# WhaleTagRecovery_3v2r1_EasyEDA.net
KiCad netlist of a schematic drawn in EasyEDA Pro
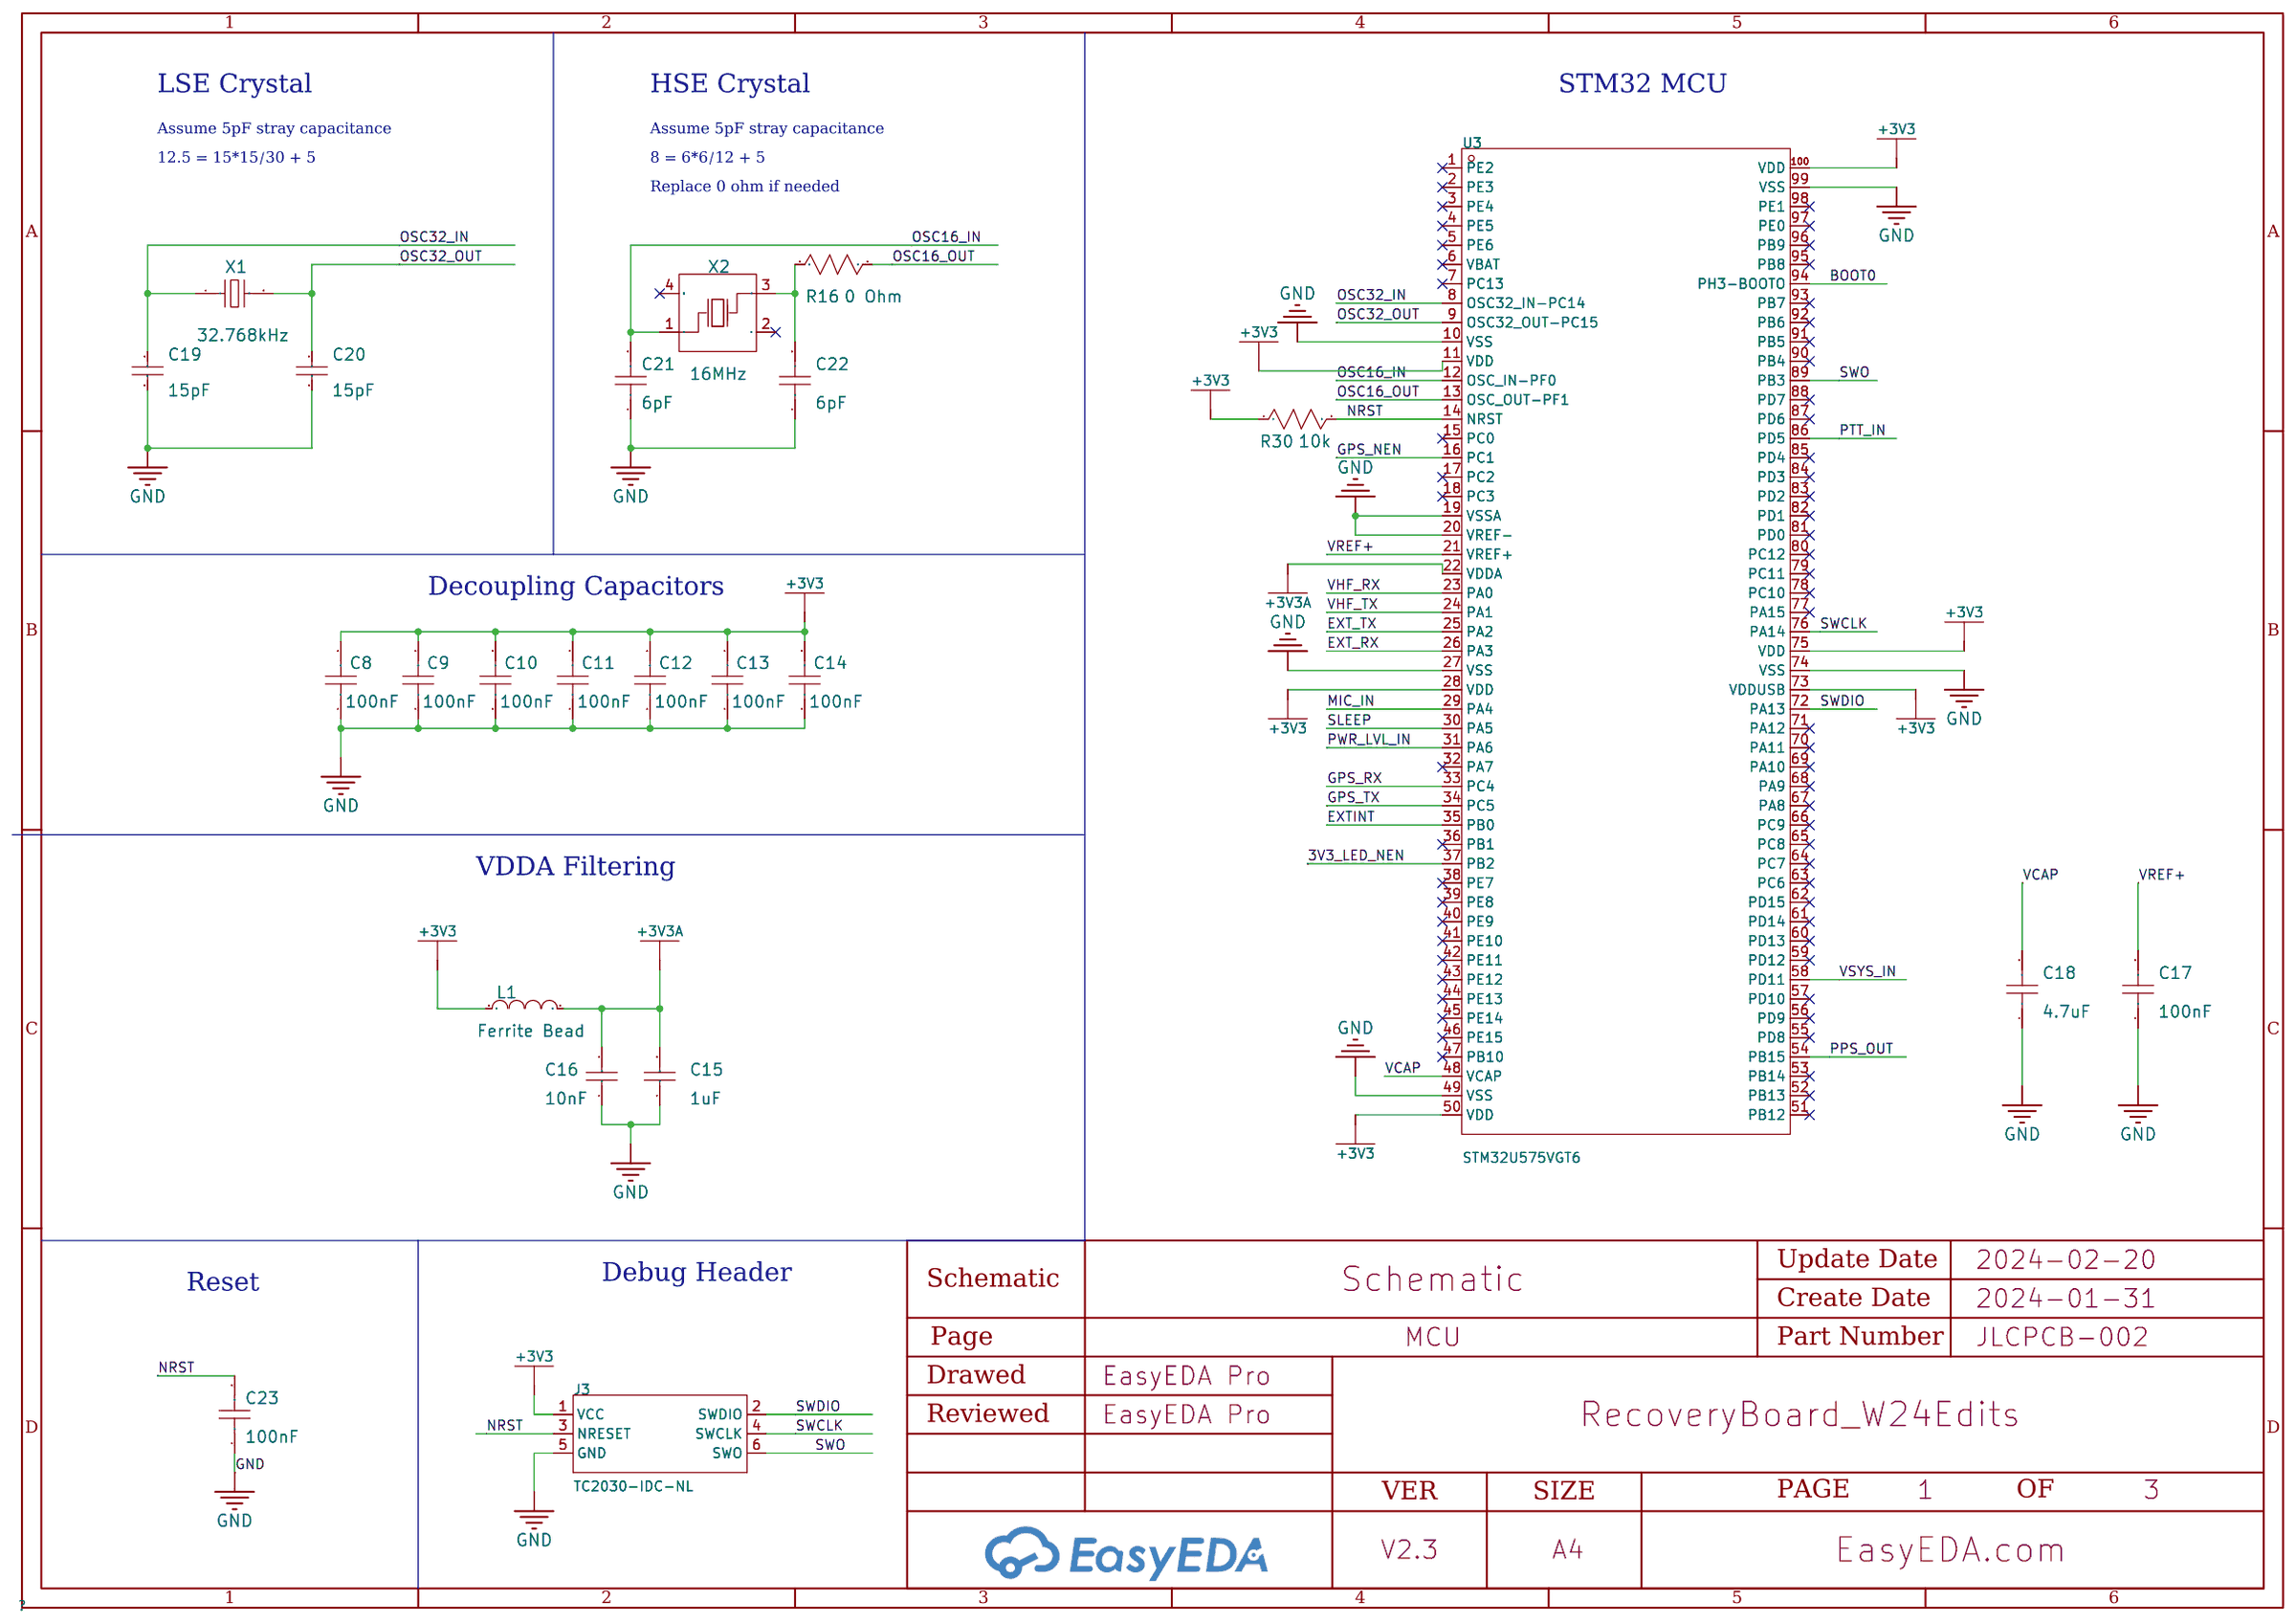
[diagram p0: MCU]
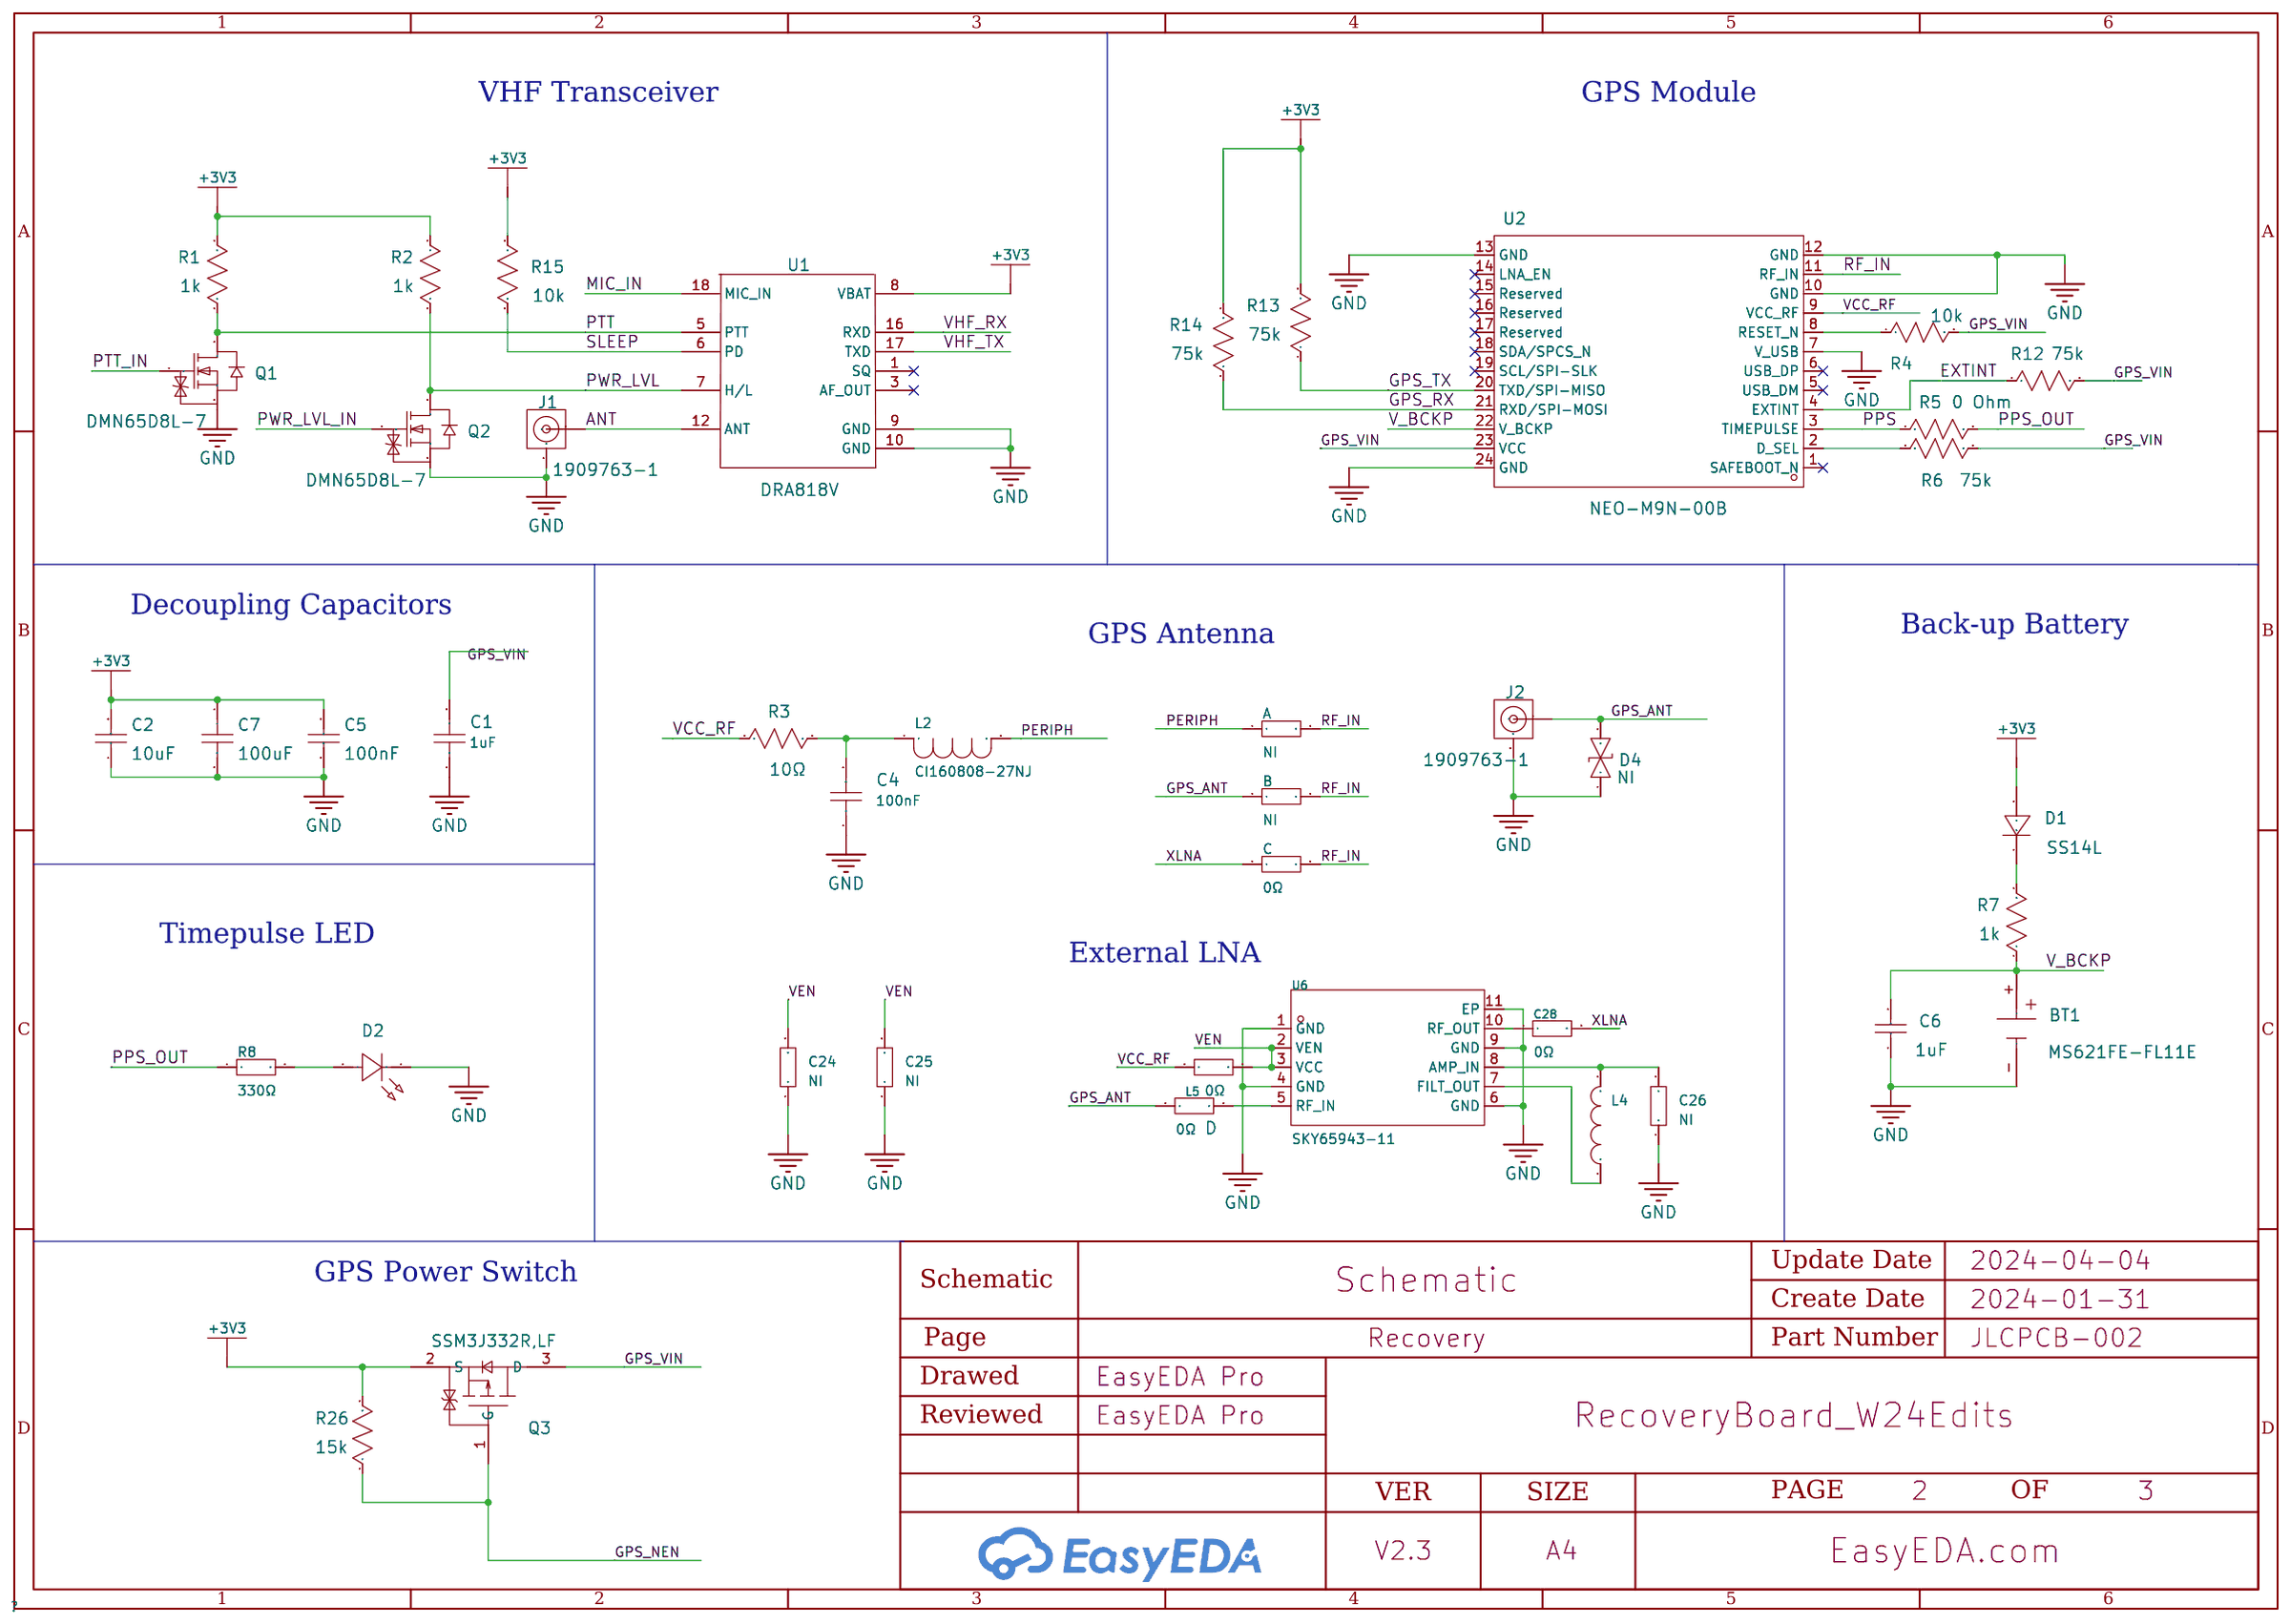
[diagram p1: Recovery]
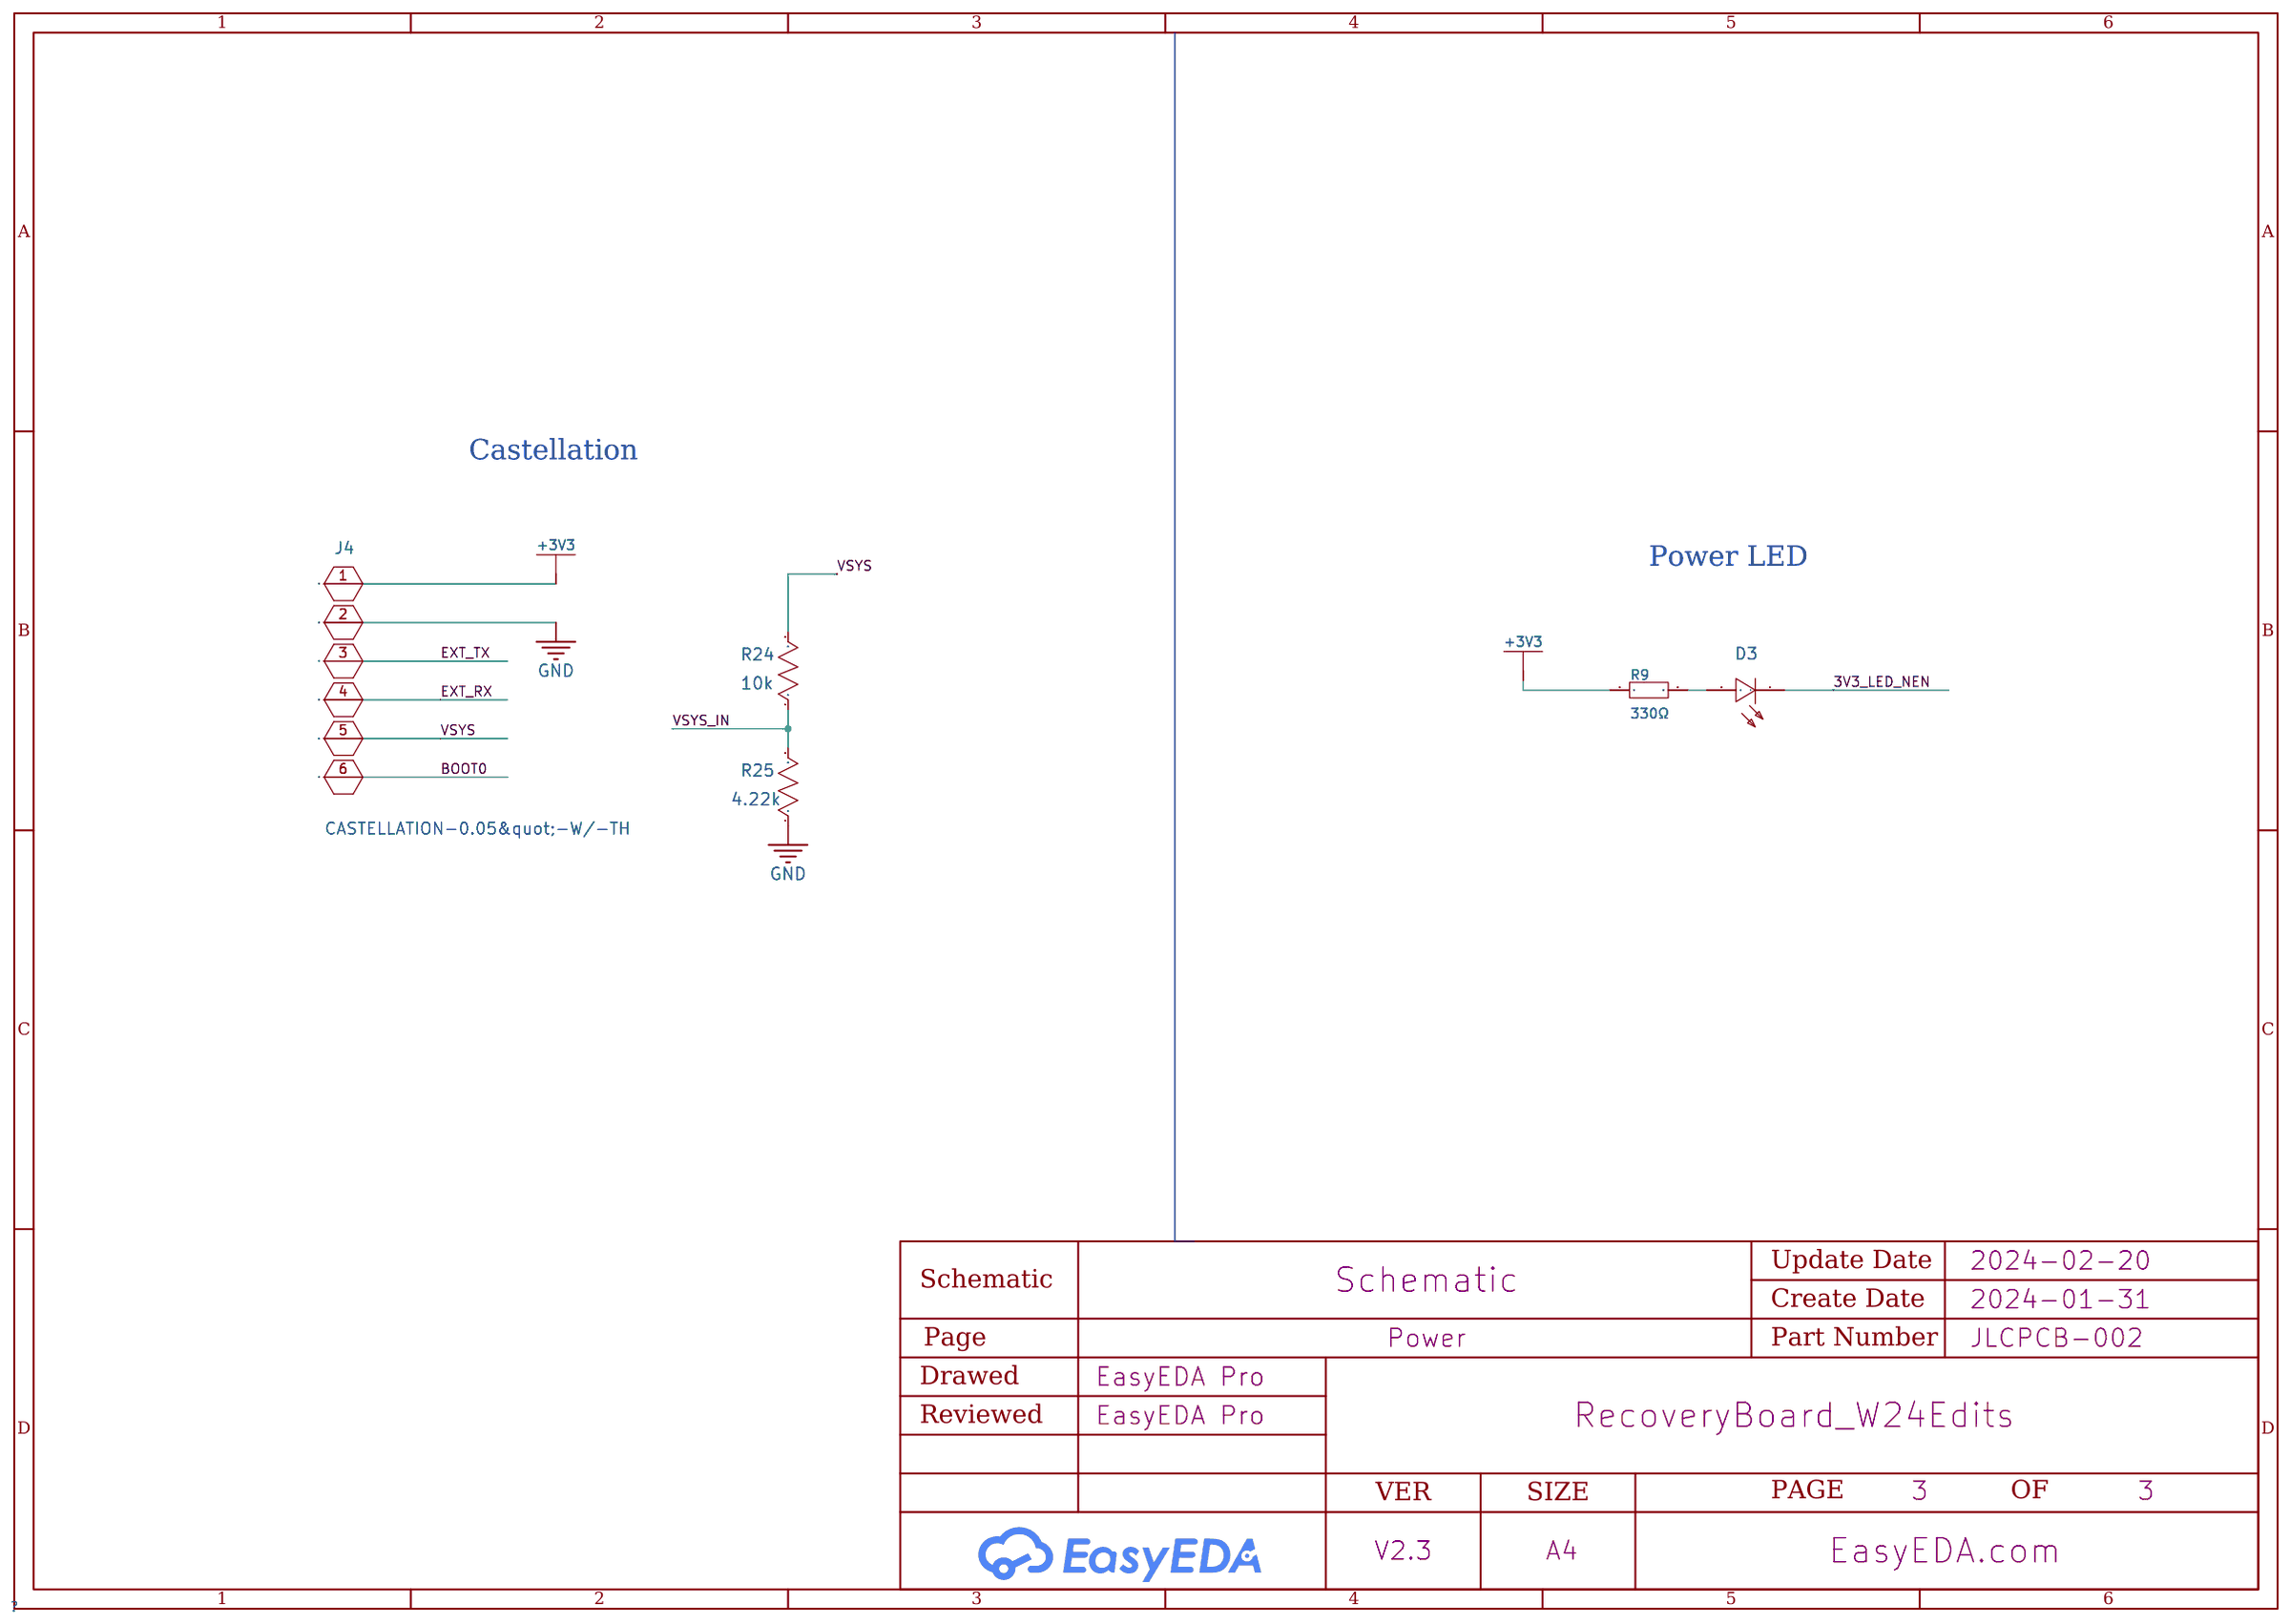
[diagram p2: Power]

(export (version "E")
  (design (tool "Eeschema 10.0.6"))
  (components
    (comp (ref "C8")
      (value "100nF")
      (footprint "easyedapro:C0402")
      (fields
        (field (name "Manufacturer Part") "GRM155R71C104KA88D")
        (field (name "Manufacturer") "muRata(村田)")
      )
      (libsource (lib "easyedapro") (part "100nF"))
    )
    (comp (ref "C9")
      (value "100nF")
      (footprint "easyedapro:C0402")
      (fields
        (field (name "Manufacturer Part") "GRM155R71C104KA88D")
        (field (name "Manufacturer") "muRata(村田)")
      )
      (libsource (lib "easyedapro") (part "100nF"))
    )
    (comp (ref "C10")
      (value "100nF")
      (footprint "easyedapro:C0402")
      (fields
        (field (name "Manufacturer Part") "GRM155R71C104KA88D")
        (field (name "Manufacturer") "muRata(村田)")
      )
      (libsource (lib "easyedapro") (part "100nF"))
    )
    (comp (ref "C11")
      (value "100nF")
      (footprint "easyedapro:C0402")
      (fields
        (field (name "Manufacturer Part") "GRM155R71C104KA88D")
        (field (name "Manufacturer") "muRata(村田)")
      )
      (libsource (lib "easyedapro") (part "100nF"))
    )
    (comp (ref "C12")
      (value "100nF")
      (footprint "easyedapro:C0402")
      (fields
        (field (name "Manufacturer Part") "GRM155R71C104KA88D")
        (field (name "Manufacturer") "muRata(村田)")
      )
      (libsource (lib "easyedapro") (part "100nF"))
    )
    (comp (ref "C13")
      (value "100nF")
      (footprint "easyedapro:C0402")
      (fields
        (field (name "Manufacturer Part") "GRM155R71C104KA88D")
        (field (name "Manufacturer") "muRata(村田)")
      )
      (libsource (lib "easyedapro") (part "100nF"))
    )
    (comp (ref "C14")
      (value "100nF")
      (footprint "easyedapro:C0402")
      (fields
        (field (name "Manufacturer Part") "GRM155R71C104KA88D")
        (field (name "Manufacturer") "muRata(村田)")
      )
      (libsource (lib "easyedapro") (part "100nF"))
    )
    (comp (ref "C15")
      (value "1uF")
      (footprint "easyedapro:C0402")
      (fields
        (field (name "Manufacturer Part") "GRM155R61E105KA12D")
        (field (name "Manufacturer") "muRata(村田)")
      )
      (libsource (lib "easyedapro") (part "1uF"))
    )
    (comp (ref "C16")
      (value "10nF")
      (footprint "easyedapro:C0402")
      (fields
        (field (name "Manufacturer Part") "GRM155R71H103KA88D")
        (field (name "Manufacturer") "muRata(村田)")
      )
      (libsource (lib "easyedapro") (part "10nF"))
    )
    (comp (ref "C17")
      (value "100nF")
      (footprint "easyedapro:C0402")
      (fields
        (field (name "Manufacturer Part") "GRM155R71C104KA88D")
        (field (name "Manufacturer") "muRata(村田)")
      )
      (libsource (lib "easyedapro") (part "100nF"))
    )
    (comp (ref "C18")
      (value "4.7uF")
      (footprint "easyedapro:C0603")
      (fields
        (field (name "Manufacturer Part") "GRM188R61A475KE15D")
        (field (name "Manufacturer") "muRata(村田)")
      )
      (libsource (lib "easyedapro") (part "4.7uF"))
    )
    (comp (ref "C19")
      (value "15pF")
      (footprint "easyedapro:C0402")
      (fields
        (field (name "Manufacturer Part") "GJM1555C1H150FB01D")
        (field (name "Manufacturer") "muRata(村田)")
      )
      (libsource (lib "easyedapro") (part "15pF"))
    )
    (comp (ref "C20")
      (value "15pF")
      (footprint "easyedapro:C0402")
      (fields
        (field (name "Manufacturer Part") "GJM1555C1H150FB01D")
        (field (name "Manufacturer") "muRata(村田)")
      )
      (libsource (lib "easyedapro") (part "15pF"))
    )
    (comp (ref "C21")
      (value "6pF")
      (footprint "easyedapro:C0402")
      (fields
        (field (name "Manufacturer Part") "GCM1555C1H6R0BA16D")
        (field (name "Manufacturer") "muRata(村田)")
      )
      (libsource (lib "easyedapro") (part "6pF"))
    )
    (comp (ref "C22")
      (value "6pF")
      (footprint "easyedapro:C0402")
      (fields
        (field (name "Manufacturer Part") "GCM1555C1H6R0BA16D")
        (field (name "Manufacturer") "muRata(村田)")
      )
      (libsource (lib "easyedapro") (part "6pF"))
    )
    (comp (ref "C23")
      (value "100nF")
      (footprint "easyedapro:C0402")
      (fields
        (field (name "Manufacturer Part") "GRM155R71C104KA88D")
        (field (name "Manufacturer") "muRata(村田)")
      )
      (libsource (lib "easyedapro") (part "100nF"))
    )
    (comp (ref "J3")
      (value "TC2030-IDC-NL")
      (footprint "easyedapro:TC2030-IDC-NL")
      (libsource (lib "easyedapro") (part "TC2030-IDC-NL"))
    )
    (comp (ref "L1")
      (value "120R")
      (footprint "easyedapro:L0603")
      (fields (field (name "Manufacturer Part") "BLM18PG121SN1D") (field (name "Manufacturer") "muRata(村田)"))
      (libsource (lib "easyedapro") (part "Ferrite Bead"))
    )
    (comp (ref "R16")
      (value "0 Ohm")
      (fields (field (name "Manufacturer Part") "0603WAF0000T5E"))
      (libsource (lib "easyedapro") (part "0 Ohm"))
    )
    (comp (ref "R30")
      (value "10k")
      (fields (field (name "Manufacturer Part") "RC0603FR-0710KL"))
      (libsource (lib "easyedapro") (part "10k"))
    )
    (comp (ref "U3")
      (value "STM32U575VGT6")
      (footprint "easyedapro:LQFP-100_L14.0-W14.0-P0.50-LS16.0-BL")
      (fields (field (name "Manufacturer") "ST(意法半导体)"))
      (libsource (lib "easyedapro") (part "STM32U575VGT6"))
    )
    (comp (ref "X1")
      (value "32.768kHz")
      (footprint "easyedapro:OSC-SMD_L3.2-W1.5")
      (fields (field (name "Manufacturer Part") "X321532768KGD2SI") (field (name "Manufacturer") "YXC(扬兴晶振)"))
      (libsource (lib "easyedapro") (part "32.768kHz"))
    )
    (comp (ref "X2")
      (value "16MHz")
      (footprint "easyedapro:CRYSTAL-SMD_4P-L2.5-W2.0-BL-A")
      (fields
        (field (name "Manufacturer Part") "NX2520SA-16MHZ-STD-CSW-5")
        (field (name "Manufacturer") "NDK")
      )
      (libsource (lib "easyedapro") (part "16MHz"))
    )
    (comp (ref "A")
      (value "NI")
      (footprint "easyedapro:R0402")
      (fields (field (name "Manufacturer Part") "ERJ2GE0R00X") (field (name "Manufacturer") "PANASONIC(松下)"))
      (libsource (lib "easyedapro") (part "ERJ2GE0R00X"))
    )
    (comp (ref "B")
      (value "NI")
      (footprint "easyedapro:R0402")
      (fields (field (name "Manufacturer Part") "ERJ2GE0R00X") (field (name "Manufacturer") "PANASONIC(松下)"))
      (libsource (lib "easyedapro") (part "ERJ2GE0R00X"))
    )
    (comp (ref "BT1") (value "MS621FE-FL11E") (libsource (lib "easyedapro") (part "MS621FE-FL11E")))
    (comp (ref "C")
      (value "0Ω")
      (footprint "easyedapro:R0402")
      (fields (field (name "Manufacturer Part") "ERJ2GE0R00X") (field (name "Manufacturer") "PANASONIC(松下)"))
      (libsource (lib "easyedapro") (part "ERJ2GE0R00X"))
    )
    (comp (ref "C1")
      (value "1uF")
      (footprint "easyedapro:C0402")
      (fields
        (field (name "Manufacturer Part") "CC0402KRX5R7BB105")
        (field (name "Manufacturer") "YAGEO(国巨)")
      )
      (libsource (lib "easyedapro") (part "CC0402KRX5R7BB105"))
    )
    (comp (ref "C2")
      (value "10uF")
      (fields
        (field (name "Manufacturer Part") "GRM188R60G106ME47D")
        (field (name "Manufacturer") "muRata(村田)")
      )
      (libsource (lib "easyedapro") (part "10uF"))
    )
    (comp (ref "C4")
      (value "100nF")
      (footprint "easyedapro:C0402")
      (fields
        (field (name "Manufacturer Part") "GCM155R71C104KA55J")
        (field (name "Manufacturer") "muRata(村田)")
      )
      (libsource (lib "easyedapro") (part "GCM155R71C104KA55J"))
    )
    (comp (ref "C5")
      (value "100nF")
      (fields
        (field (name "Manufacturer Part") "CC0402ZRY5V7BB104")
        (field (name "Manufacturer") "YAGEO(国巨)")
      )
      (libsource (lib "easyedapro") (part "100nF"))
    )
    (comp (ref "C6")
      (value "1uF")
      (footprint "easyedapro:C0402")
      (fields
        (field (name "Manufacturer Part") "GRM155R61E105KA12D")
        (field (name "Manufacturer") "muRata(村田)")
      )
      (libsource (lib "easyedapro") (part "1uF"))
    )
    (comp (ref "C7")
      (value "100uF")
      (fields
        (field (name "Manufacturer Part") "GRM32ER60J107ME20L")
        (field (name "Manufacturer") "muRata(村田)")
      )
      (libsource (lib "easyedapro") (part "100uF"))
    )
    (comp (ref "C24")
      (value "NI")
      (footprint "easyedapro:R0402")
      (fields (field (name "Manufacturer Part") "ERJ2GE0R00X") (field (name "Manufacturer") "PANASONIC(松下)"))
      (libsource (lib "easyedapro") (part "ERJ2GE0R00X"))
    )
    (comp (ref "C25")
      (value "NI")
      (footprint "easyedapro:R0402")
      (fields (field (name "Manufacturer Part") "ERJ2GE0R00X") (field (name "Manufacturer") "PANASONIC(松下)"))
      (libsource (lib "easyedapro") (part "ERJ2GE0R00X"))
    )
    (comp (ref "C26")
      (value "NI")
      (footprint "easyedapro:R0402")
      (fields (field (name "Manufacturer Part") "ERJ2GE0R00X") (field (name "Manufacturer") "PANASONIC(松下)"))
      (libsource (lib "easyedapro") (part "ERJ2GE0R00X"))
    )
    (comp (ref "C28")
      (value "0Ω")
      (footprint "easyedapro:R0402")
      (fields (field (name "Manufacturer Part") "ERJ2GE0R00X") (field (name "Manufacturer") "PANASONIC(松下)"))
      (libsource (lib "easyedapro") (part "ERJ2GE0R00X"))
    )
    (comp (ref "D")
      (value "0Ω")
      (footprint "easyedapro:R0402")
      (fields (field (name "Manufacturer Part") "ERJ2GE0R00X") (field (name "Manufacturer") "PANASONIC(松下)"))
      (libsource (lib "easyedapro") (part "ERJ2GE0R00X"))
    )
    (comp (ref "D1")
      (value "SS14L")
      (fields (field (name "Manufacturer Part") "SS14L_R1_00001") (field (name "Manufacturer") "PANJIT(强茂)"))
      (libsource (lib "easyedapro") (part "SS14L"))
    )
    (comp (ref "D2")
      (value "16-213/BHC-ZL1M2B6Y/3T")
      (fields (field (name "Manufacturer") "EVERLIGHT(亿光)"))
      (libsource (lib "easyedapro") (part "16-213/BHC-ZL1M2B6Y/3T"))
    )
    (comp (ref "D4")
      (value "NI")
      (fields (field (name "Manufacturer Part") "LESD3Z5.0CMT1G") (field (name "Manufacturer") "LRC(乐山无线电)"))
      (libsource (lib "easyedapro") (part "LESD3Z5.0CMT1G"))
    )
    (comp (ref "J1")
      (value "1909763-1")
      (fields (field (name "Manufacturer") "TEConnectivity(美国泰科)"))
      (libsource (lib "easyedapro") (part "1909763-1"))
    )
    (comp (ref "J2")
      (value "1909763-1")
      (fields (field (name "Manufacturer") "TEConnectivity(美国泰科)"))
      (libsource (lib "easyedapro") (part "1909763-1"))
    )
    (comp (ref "L2")
      (value "CI160808-27NJ")
      (footprint "easyedapro:IND_BOURNS_CI160808")
      (libsource (lib "easyedapro") (part "CI160808-27NJ_IND_BOURNS_CI160808"))
    )
    (comp (ref "L4")
      (value "~")
      (footprint "easyedapro:INDC1006X60N")
      (libsource (lib "easyedapro") (part "LQW15AN9N1J00D_"))
    )
    (comp (ref "L5")
      (value "0Ω")
      (footprint "easyedapro:R0402")
      (fields (field (name "Manufacturer Part") "ERJ2GE0R00X") (field (name "Manufacturer") "PANASONIC(松下)"))
      (libsource (lib "easyedapro") (part "ERJ2GE0R00X"))
    )
    (comp (ref "Q1")
      (value "DMN65D8L-7")
      (fields (field (name "Manufacturer") "DIODES(美台)"))
      (libsource (lib "easyedapro") (part "DMN65D8L-7"))
    )
    (comp (ref "Q2")
      (value "DMN65D8L-7")
      (fields (field (name "Manufacturer") "DIODES(美台)"))
      (libsource (lib "easyedapro") (part "DMN65D8L-7"))
    )
    (comp (ref "Q3")
      (value "SSM3J332R,LF")
      (footprint "easyedapro:SOT-23F_L2.9-W1.8-P0.95-LS2.4-BR")
      (fields (field (name "Manufacturer") "TOSHIBA"))
      (libsource (lib "easyedapro") (part "SSM3J332R,LF"))
    )
    (comp (ref "R1") (value "1k") (libsource (lib "easyedapro") (part "1k")))
    (comp (ref "R2") (value "1k") (libsource (lib "easyedapro") (part "1k")))
    (comp (ref "R3")
      (value "10Ω")
      (fields (field (name "Manufacturer Part") "ESR03EZPJ100") (field (name "Manufacturer") "ROHM(罗姆)"))
      (libsource (lib "easyedapro") (part "10"))
    )
    (comp (ref "R4")
      (value "10k")
      (fields (field (name "Manufacturer Part") "RC0603FR-0710KL"))
      (libsource (lib "easyedapro") (part "10k"))
    )
    (comp (ref "R5")
      (value "0 Ohm")
      (fields (field (name "Manufacturer Part") "0603WAF0000T5E"))
      (libsource (lib "easyedapro") (part "0 Ohm"))
    )
    (comp (ref "R6")
      (value "75k")
      (fields (field (name "Manufacturer Part") "RC0603FR-0775KL"))
      (libsource (lib "easyedapro") (part "75k"))
    )
    (comp (ref "R7") (value "1k") (libsource (lib "easyedapro") (part "1k")))
    (comp (ref "R8")
      (value "330Ω")
      (footprint "easyedapro:R0603")
      (fields (field (name "Manufacturer Part") "RC0603JR-07330RL") (field (name "Manufacturer") "YAGEO(国巨)"))
      (libsource (lib "easyedapro") (part "RC0603JR-07330RL"))
    )
    (comp (ref "R12")
      (value "75k")
      (fields (field (name "Manufacturer Part") "RC0603FR-0775KL"))
      (libsource (lib "easyedapro") (part "75k"))
    )
    (comp (ref "R13")
      (value "75k")
      (fields (field (name "Manufacturer Part") "RC0603FR-0775KL"))
      (libsource (lib "easyedapro") (part "75k"))
    )
    (comp (ref "R14")
      (value "75k")
      (fields (field (name "Manufacturer Part") "RC0603FR-0775KL"))
      (libsource (lib "easyedapro") (part "75k"))
    )
    (comp (ref "R15")
      (value "10k")
      (fields (field (name "Manufacturer Part") "RC0603FR-0710KL"))
      (libsource (lib "easyedapro") (part "10k"))
    )
    (comp (ref "R26")
      (value "15k")
      (fields (field (name "Manufacturer Part") "0402WGF1502TCE"))
      (libsource (lib "easyedapro") (part "10"))
    )
    (comp (ref "U1") (value "DRA818V") (libsource (lib "easyedapro") (part "DRA818V")))
    (comp (ref "U2") (value "NEO-M9N-00B") (libsource (lib "easyedapro") (part "NEO-M9N-00B")))
    (comp (ref "U6")
      (value "SKY65943-11")
      (footprint "easyedapro:MCM-10_L2.5-W2.5-P0.50-BL-EP")
      (fields (field (name "Manufacturer") "SKYWORKS"))
      (libsource (lib "easyedapro") (part "SKY65943-11"))
    )
    (comp (ref "D3")
      (value "16-213/SDRC/S530-A3/TR8")
      (fields
        (field (name "Manufacturer Part") "16-213SDRC/S530-A3/TR8")
        (field (name "Manufacturer") "EVERLIGHT(亿光)")
      )
      (libsource (lib "easyedapro") (part "16-213/SDRC/S530-A3/TR8"))
    )
    (comp (ref "J4")
      (value "CASTELLATION-0.05&quot;-W/-TH")
      (footprint "easyedapro:CASTELLATION-0.05\"-W/-TH")
      (libsource (lib "easyedapro") (part "CASTELLATION-0.05{dblquote}-W/-TH"))
    )
    (comp (ref "R9")
      (value "330Ω")
      (footprint "easyedapro:R0603")
      (fields (field (name "Manufacturer Part") "RC0603JR-07330RL") (field (name "Manufacturer") "YAGEO(国巨)"))
      (libsource (lib "easyedapro") (part "RC0603JR-07330RL"))
    )
    (comp (ref "R24")
      (value "10k")
      (fields (field (name "Manufacturer Part") "TR0402D10KQ1025"))
      (libsource (lib "easyedapro") (part "10"))
    )
    (comp (ref "R25")
      (value "4.22k")
      (fields (field (name "Manufacturer Part") "RT0402BRD074K22L"))
      (libsource (lib "easyedapro") (part "10"))
    )
  )
  (nets
    (net (code "1") (name "+3V3") (class "Default")
      (node (ref "C10") (pin "2") (pinfunction "2_2") (pintype "input"))
      (node (ref "C11") (pin "2") (pinfunction "2_2") (pintype "input"))
      (node (ref "C12") (pin "2") (pinfunction "2_2") (pintype "input"))
      (node (ref "C13") (pin "2") (pinfunction "2_2") (pintype "input"))
      (node (ref "C14") (pin "2") (pinfunction "2_2") (pintype "input"))
      (node (ref "C2") (pin "2") (pinfunction "2_2") (pintype "input"))
      (node (ref "C5") (pin "2") (pinfunction "2_2") (pintype "input"))
      (node (ref "C7") (pin "1") (pinfunction "1_1") (pintype "input"))
      (node (ref "C8") (pin "2") (pinfunction "2_2") (pintype "input"))
      (node (ref "C9") (pin "2") (pinfunction "2_2") (pintype "input"))
      (node (ref "D1") (pin "2") (pinfunction "A_2") (pintype "input"))
      (node (ref "J3") (pin "1") (pinfunction "VCC_1") (pintype "bidirectional"))
      (node (ref "J4") (pin "1") (pinfunction "1_1") (pintype "input"))
      (node (ref "L1") (pin "2") (pinfunction "2_2") (pintype "input"))
      (node (ref "Q3") (pin "2") (pinfunction "S_2") (pintype "input"))
      (node (ref "R1") (pin "2") (pinfunction "2_2") (pintype "input"))
      (node (ref "R13") (pin "2") (pinfunction "2_2") (pintype "input"))
      (node (ref "R14") (pin "2") (pinfunction "2_2") (pintype "input"))
      (node (ref "R15") (pin "2") (pinfunction "2_2") (pintype "input"))
      (node (ref "R2") (pin "2") (pinfunction "2_2") (pintype "input"))
      (node (ref "R26") (pin "2") (pinfunction "2_2") (pintype "input"))
      (node (ref "R30") (pin "1") (pinfunction "1_1") (pintype "input"))
      (node (ref "R9") (pin "1") (pinfunction "1_1") (pintype "input"))
      (node (ref "U1") (pin "8") (pinfunction "VBAT_8") (pintype "bidirectional"))
      (node (ref "U3") (pin "100") (pinfunction "VDD_100") (pintype "input"))
      (node (ref "U3") (pin "11") (pinfunction "VDD_11") (pintype "input"))
      (node (ref "U3") (pin "28") (pinfunction "VDD_28") (pintype "input"))
      (node (ref "U3") (pin "50") (pinfunction "VDD_50") (pintype "input"))
      (node (ref "U3") (pin "73") (pinfunction "VDDUSB_73") (pintype "input"))
      (node (ref "U3") (pin "75") (pinfunction "VDD_75") (pintype "input"))
    )
    (net (code "2") (name "+3V3A") (class "Default")
      (node (ref "C15") (pin "2") (pinfunction "2_2") (pintype "input"))
      (node (ref "C16") (pin "2") (pinfunction "2_2") (pintype "input"))
      (node (ref "L1") (pin "1") (pinfunction "1_1") (pintype "input"))
      (node (ref "U3") (pin "22") (pinfunction "VDDA_22") (pintype "input"))
    )
    (net (code "3") (name "3V3_LED_NEN") (class "Default")
      (node (ref "D3") (pin "1") (pinfunction "-_1") (pintype "input"))
      (node (ref "U3") (pin "37") (pinfunction "PB2_37") (pintype "input"))
    )
    (net (code "4") (name "ANT") (class "Default")
      (node (ref "J1") (pin "1") (pinfunction "1_1") (pintype "input"))
      (node (ref "U1") (pin "12") (pinfunction "ANT_12") (pintype "bidirectional"))
    )
    (net (code "5") (name "BOOT0") (class "Default")
      (node (ref "J4") (pin "6") (pinfunction "1_6") (pintype "input"))
      (node (ref "U3") (pin "94") (pinfunction "PH3-BOOTO_94") (pintype "input"))
    )
    (net (code "6") (name "EXTINT") (class "Default")
      (node (ref "R12") (pin "1") (pinfunction "1_1") (pintype "input"))
      (node (ref "U2") (pin "4") (pinfunction "EXTINT_4") (pintype "input"))
      (node (ref "U3") (pin "35") (pinfunction "PB0_35") (pintype "input"))
    )
    (net (code "7") (name "EXT_RX") (class "Default")
      (node (ref "J4") (pin "4") (pinfunction "1_4") (pintype "input"))
      (node (ref "U3") (pin "26") (pinfunction "PA3_26") (pintype "input"))
    )
    (net (code "8") (name "EXT_TX") (class "Default")
      (node (ref "J4") (pin "3") (pinfunction "1_3") (pintype "input"))
      (node (ref "U3") (pin "25") (pinfunction "PA2_25") (pintype "input"))
    )
    (net (code "9") (name "GND") (class "Default")
      (node (ref "BT1") (pin "-") (pinfunction "-_-") (pintype "bidirectional"))
      (node (ref "C1") (pin "1") (pinfunction "1_1") (pintype "input"))
      (node (ref "C10") (pin "1") (pinfunction "1_1") (pintype "input"))
      (node (ref "C11") (pin "1") (pinfunction "1_1") (pintype "input"))
      (node (ref "C12") (pin "1") (pinfunction "1_1") (pintype "input"))
      (node (ref "C13") (pin "1") (pinfunction "1_1") (pintype "input"))
      (node (ref "C14") (pin "1") (pinfunction "1_1") (pintype "input"))
      (node (ref "C15") (pin "1") (pinfunction "1_1") (pintype "input"))
      (node (ref "C16") (pin "1") (pinfunction "1_1") (pintype "input"))
      (node (ref "C17") (pin "1") (pinfunction "1_1") (pintype "input"))
      (node (ref "C18") (pin "1") (pinfunction "1_1") (pintype "input"))
      (node (ref "C19") (pin "1") (pinfunction "1_1") (pintype "input"))
      (node (ref "C2") (pin "1") (pinfunction "1_1") (pintype "input"))
      (node (ref "C20") (pin "1") (pinfunction "1_1") (pintype "input"))
      (node (ref "C21") (pin "1") (pinfunction "1_1") (pintype "input"))
      (node (ref "C22") (pin "1") (pinfunction "1_1") (pintype "input"))
      (node (ref "C23") (pin "1") (pinfunction "1_1") (pintype "input"))
      (node (ref "C24") (pin "1") (pinfunction "1_1") (pintype "input"))
      (node (ref "C25") (pin "1") (pinfunction "1_1") (pintype "input"))
      (node (ref "C26") (pin "1") (pinfunction "1_1") (pintype "input"))
      (node (ref "C4") (pin "1") (pinfunction "1_1") (pintype "input"))
      (node (ref "C5") (pin "1") (pinfunction "1_1") (pintype "input"))
      (node (ref "C6") (pin "1") (pinfunction "1_1") (pintype "input"))
      (node (ref "C7") (pin "2") (pinfunction "2_2") (pintype "input"))
      (node (ref "C8") (pin "1") (pinfunction "1_1") (pintype "input"))
      (node (ref "C9") (pin "1") (pinfunction "1_1") (pintype "input"))
      (node (ref "D2") (pin "1") (pinfunction "K_1") (pintype "input"))
      (node (ref "D4") (pin "1") (pinfunction "1_1") (pintype "input"))
      (node (ref "J1") (pin "2") (pinfunction "2_2") (pintype "input"))
      (node (ref "J2") (pin "2") (pinfunction "2_2") (pintype "input"))
      (node (ref "J3") (pin "5") (pinfunction "GND_5") (pintype "bidirectional"))
      (node (ref "J4") (pin "2") (pinfunction "1_2") (pintype "input"))
      (node (ref "Q1") (pin "2") (pinfunction "S_2") (pintype "input"))
      (node (ref "Q2") (pin "2") (pinfunction "S_2") (pintype "input"))
      (node (ref "R25") (pin "1") (pinfunction "1_1") (pintype "input"))
      (node (ref "U1") (pin "10") (pinfunction "GND_10") (pintype "bidirectional"))
      (node (ref "U1") (pin "9") (pinfunction "GND_9") (pintype "bidirectional"))
      (node (ref "U2") (pin "10") (pinfunction "GND_10") (pintype "input"))
      (node (ref "U2") (pin "12") (pinfunction "GND_12") (pintype "input"))
      (node (ref "U2") (pin "13") (pinfunction "GND_13") (pintype "input"))
      (node (ref "U2") (pin "24") (pinfunction "GND_24") (pintype "input"))
      (node (ref "U2") (pin "7") (pinfunction "V_USB_7") (pintype "input"))
      (node (ref "U3") (pin "10") (pinfunction "VSS_10") (pintype "input"))
      (node (ref "U3") (pin "19") (pinfunction "VSSA_19") (pintype "input"))
      (node (ref "U3") (pin "20") (pinfunction "VREF-_20") (pintype "input"))
      (node (ref "U3") (pin "27") (pinfunction "VSS_27") (pintype "input"))
      (node (ref "U3") (pin "49") (pinfunction "VSS_49") (pintype "input"))
      (node (ref "U3") (pin "74") (pinfunction "VSS_74") (pintype "input"))
      (node (ref "U3") (pin "99") (pinfunction "VSS_99") (pintype "input"))
      (node (ref "U6") (pin "1") (pinfunction "GND_1") (pintype "input"))
      (node (ref "U6") (pin "11") (pinfunction "EP_11") (pintype "input"))
      (node (ref "U6") (pin "4") (pinfunction "GND_4") (pintype "input"))
      (node (ref "U6") (pin "6") (pinfunction "GND_6") (pintype "input"))
      (node (ref "U6") (pin "9") (pinfunction "GND_9") (pintype "input"))
    )
    (net (code "10") (name "GPS_ANT") (class "Default")
      (node (ref "B") (pin "1") (pinfunction "1_1") (pintype "input"))
      (node (ref "D") (pin "1") (pinfunction "1_1") (pintype "input"))
      (node (ref "D4") (pin "2") (pinfunction "2_2") (pintype "input"))
      (node (ref "J2") (pin "1") (pinfunction "1_1") (pintype "input"))
    )
    (net (code "11") (name "GPS_NEN") (class "Default")
      (node (ref "Q3") (pin "1") (pinfunction "G_1") (pintype "input"))
      (node (ref "R26") (pin "1") (pinfunction "1_1") (pintype "input"))
      (node (ref "U3") (pin "16") (pinfunction "PC1_16") (pintype "input"))
    )
    (net (code "12") (name "GPS_RX") (class "Default")
      (node (ref "R14") (pin "1") (pinfunction "1_1") (pintype "input"))
      (node (ref "U2") (pin "21") (pinfunction "RXD/SPI-MOSI_21") (pintype "input"))
      (node (ref "U3") (pin "33") (pinfunction "PC4_33") (pintype "input"))
    )
    (net (code "13") (name "GPS_TX") (class "Default")
      (node (ref "R13") (pin "1") (pinfunction "1_1") (pintype "input"))
      (node (ref "U2") (pin "20") (pinfunction "TXD/SPI-MISO_20") (pintype "input"))
      (node (ref "U3") (pin "34") (pinfunction "PC5_34") (pintype "input"))
    )
    (net (code "14") (name "GPS_VIN") (class "Default")
      (node (ref "C1") (pin "2") (pinfunction "2_2") (pintype "input"))
      (node (ref "Q3") (pin "3") (pinfunction "D_3") (pintype "input"))
      (node (ref "R12") (pin "2") (pinfunction "2_2") (pintype "input"))
      (node (ref "R4") (pin "2") (pinfunction "2_2") (pintype "input"))
      (node (ref "R6") (pin "2") (pinfunction "2_2") (pintype "input"))
      (node (ref "U2") (pin "23") (pinfunction "VCC_23") (pintype "input"))
    )
    (net (code "15") (name "MIC_IN") (class "Default")
      (node (ref "U1") (pin "18") (pinfunction "MIC_IN_18") (pintype "bidirectional"))
      (node (ref "U3") (pin "29") (pinfunction "PA4_29") (pintype "input"))
    )
    (net (code "16") (name "NRST") (class "Default")
      (node (ref "C23") (pin "2") (pinfunction "2_2") (pintype "input"))
      (node (ref "J3") (pin "3") (pinfunction "NRESET_3") (pintype "bidirectional"))
      (node (ref "R30") (pin "2") (pinfunction "2_2") (pintype "input"))
      (node (ref "U3") (pin "14") (pinfunction "NRST_14") (pintype "input"))
    )
    (net (code "17") (name "Net-(C4-Pad2)") (class "Default")
      (node (ref "C4") (pin "2") (pinfunction "2_2") (pintype "input"))
      (node (ref "L2") (pin "1") (pinfunction "1_1") (pintype "unspecified"))
      (node (ref "R3") (pin "2") (pinfunction "2_2") (pintype "input"))
    )
    (net (code "18") (name "Net-(D1-C)") (class "Default")
      (node (ref "D1") (pin "1") (pinfunction "C_1") (pintype "input"))
      (node (ref "R7") (pin "2") (pinfunction "2_2") (pintype "input"))
    )
    (net (code "19") (name "Net-(D2-A)") (class "Default")
      (node (ref "D2") (pin "2") (pinfunction "A_2") (pintype "input"))
      (node (ref "R8") (pin "2") (pinfunction "2_2") (pintype "input"))
    )
    (net (code "20") (name "Net-(D3-+)") (class "Default")
      (node (ref "D3") (pin "2") (pinfunction "+_2") (pintype "input"))
      (node (ref "R9") (pin "2") (pinfunction "2_2") (pintype "input"))
    )
    (net (code "21") (name "Net-(U2-D_SEL)") (class "Default")
      (node (ref "R6") (pin "1") (pinfunction "1_1") (pintype "input"))
      (node (ref "U2") (pin "2") (pinfunction "D_SEL_2") (pintype "input"))
    )
    (net (code "22") (name "Net-(U2-RESET_N)") (class "Default")
      (node (ref "R4") (pin "1") (pinfunction "1_1") (pintype "input"))
      (node (ref "U2") (pin "8") (pinfunction "RESET_N_8") (pintype "input"))
    )
    (net (code "23") (name "Net-(U6-AMP_IN)") (class "Default")
      (node (ref "C26") (pin "2") (pinfunction "2_2") (pintype "input"))
      (node (ref "L4") (pin "2") (pinfunction "2_2") (pintype "unspecified"))
      (node (ref "U6") (pin "8") (pinfunction "AMP_IN_8") (pintype "input"))
    )
    (net (code "24") (name "Net-(U6-FILT_OUT)") (class "Default")
      (node (ref "L4") (pin "1") (pinfunction "1_1") (pintype "unspecified"))
      (node (ref "U6") (pin "7") (pinfunction "FILT_OUT_7") (pintype "input"))
    )
    (net (code "25") (name "Net-(U6-RF_IN)") (class "Default")
      (node (ref "D") (pin "2") (pinfunction "2_2") (pintype "input"))
      (node (ref "U6") (pin "5") (pinfunction "RF_IN_5") (pintype "input"))
    )
    (net (code "26") (name "Net-(U6-RF_OUT)") (class "Default")
      (node (ref "C28") (pin "1") (pinfunction "1_1") (pintype "input"))
      (node (ref "U6") (pin "10") (pinfunction "RF_OUT_10") (pintype "input"))
    )
    (net (code "27") (name "Net-(X2-2)") (class "Default")
      (node (ref "C22") (pin "2") (pinfunction "2_2") (pintype "input"))
      (node (ref "R16") (pin "1") (pinfunction "1_1") (pintype "input"))
      (node (ref "X2") (pin "3") (pinfunction "2_3") (pintype "input"))
    )
    (net (code "28") (name "OSC16_IN") (class "Default")
      (node (ref "C21") (pin "2") (pinfunction "2_2") (pintype "input"))
      (node (ref "U3") (pin "12") (pinfunction "OSC_IN-PF0_12") (pintype "input"))
      (node (ref "X2") (pin "1") (pinfunction "1_1") (pintype "input"))
    )
    (net (code "29") (name "OSC16_OUT") (class "Default")
      (node (ref "R16") (pin "2") (pinfunction "2_2") (pintype "input"))
      (node (ref "U3") (pin "13") (pinfunction "OSC_OUT-PF1_13") (pintype "input"))
    )
    (net (code "30") (name "OSC32_IN") (class "Default")
      (node (ref "C19") (pin "2") (pinfunction "2_2") (pintype "input"))
      (node (ref "U3") (pin "8") (pinfunction "OSC32_IN-PC14_8") (pintype "input"))
      (node (ref "X1") (pin "1") (pinfunction "1_1") (pintype "input"))
    )
    (net (code "31") (name "OSC32_OUT") (class "Default")
      (node (ref "C20") (pin "2") (pinfunction "2_2") (pintype "input"))
      (node (ref "U3") (pin "9") (pinfunction "OSC32_OUT-PC15_9") (pintype "input"))
      (node (ref "X1") (pin "2") (pinfunction "2_2") (pintype "input"))
    )
    (net (code "32") (name "PERIPH") (class "Default")
      (node (ref "A") (pin "1") (pinfunction "1_1") (pintype "input"))
      (node (ref "L2") (pin "2") (pinfunction "2_2") (pintype "unspecified"))
    )
    (net (code "33") (name "PPS") (class "Default")
      (node (ref "R5") (pin "1") (pinfunction "1_1") (pintype "input"))
      (node (ref "U2") (pin "3") (pinfunction "TIMEPULSE_3") (pintype "input"))
    )
    (net (code "34") (name "PPS_OUT") (class "Default")
      (node (ref "R5") (pin "2") (pinfunction "2_2") (pintype "input"))
      (node (ref "R8") (pin "1") (pinfunction "1_1") (pintype "input"))
      (node (ref "U3") (pin "54") (pinfunction "PB15_54") (pintype "input"))
    )
    (net (code "35") (name "PTT") (class "Default")
      (node (ref "Q1") (pin "3") (pinfunction "D_3") (pintype "input"))
      (node (ref "R1") (pin "1") (pinfunction "1_1") (pintype "input"))
      (node (ref "U1") (pin "5") (pinfunction "PTT_5") (pintype "bidirectional"))
    )
    (net (code "36") (name "PTT_IN") (class "Default")
      (node (ref "Q1") (pin "1") (pinfunction "G_1") (pintype "input"))
      (node (ref "U3") (pin "86") (pinfunction "PD5_86") (pintype "input"))
    )
    (net (code "37") (name "PWR_LVL") (class "Default")
      (node (ref "Q2") (pin "3") (pinfunction "D_3") (pintype "input"))
      (node (ref "R2") (pin "1") (pinfunction "1_1") (pintype "input"))
      (node (ref "U1") (pin "7") (pinfunction "H/L_7") (pintype "bidirectional"))
    )
    (net (code "38") (name "PWR_LVL_IN") (class "Default")
      (node (ref "Q2") (pin "1") (pinfunction "G_1") (pintype "input"))
      (node (ref "U3") (pin "31") (pinfunction "PA6_31") (pintype "input"))
    )
    (net (code "39") (name "RF_IN") (class "Default")
      (node (ref "A") (pin "2") (pinfunction "2_2") (pintype "input"))
      (node (ref "B") (pin "2") (pinfunction "2_2") (pintype "input"))
      (node (ref "C") (pin "2") (pinfunction "2_2") (pintype "input"))
      (node (ref "U2") (pin "11") (pinfunction "RF_IN_11") (pintype "input"))
    )
    (net (code "40") (name "SLEEP") (class "Default")
      (node (ref "R15") (pin "1") (pinfunction "1_1") (pintype "input"))
      (node (ref "U1") (pin "6") (pinfunction "PD_6") (pintype "bidirectional"))
      (node (ref "U3") (pin "30") (pinfunction "PA5_30") (pintype "input"))
    )
    (net (code "41") (name "SWCLK") (class "Default")
      (node (ref "J3") (pin "4") (pinfunction "SWCLK_4") (pintype "bidirectional"))
      (node (ref "U3") (pin "76") (pinfunction "PA14_76") (pintype "input"))
    )
    (net (code "42") (name "SWDIO") (class "Default")
      (node (ref "J3") (pin "2") (pinfunction "SWDIO_2") (pintype "bidirectional"))
      (node (ref "U3") (pin "72") (pinfunction "PA13_72") (pintype "input"))
    )
    (net (code "43") (name "SWO") (class "Default")
      (node (ref "J3") (pin "6") (pinfunction "SWO_6") (pintype "bidirectional"))
      (node (ref "U3") (pin "89") (pinfunction "PB3_89") (pintype "input"))
    )
    (net (code "44") (name "VCAP") (class "Default")
      (node (ref "C18") (pin "2") (pinfunction "2_2") (pintype "input"))
      (node (ref "U3") (pin "48") (pinfunction "VCAP_48") (pintype "input"))
    )
    (net (code "45") (name "VCC_RF") (class "Default")
      (node (ref "L5") (pin "1") (pinfunction "1_1") (pintype "input"))
      (node (ref "R3") (pin "1") (pinfunction "1_1") (pintype "input"))
      (node (ref "U2") (pin "9") (pinfunction "VCC_RF_9") (pintype "input"))
    )
    (net (code "46") (name "VEN") (class "Default")
      (node (ref "C24") (pin "2") (pinfunction "2_2") (pintype "input"))
      (node (ref "C25") (pin "2") (pinfunction "2_2") (pintype "input"))
      (node (ref "L5") (pin "2") (pinfunction "2_2") (pintype "input"))
      (node (ref "U6") (pin "2") (pinfunction "VEN_2") (pintype "input"))
      (node (ref "U6") (pin "3") (pinfunction "VCC_3") (pintype "input"))
    )
    (net (code "47") (name "VHF_RX") (class "Default")
      (node (ref "U1") (pin "16") (pinfunction "RXD_16") (pintype "bidirectional"))
      (node (ref "U3") (pin "23") (pinfunction "PA0_23") (pintype "input"))
    )
    (net (code "48") (name "VHF_TX") (class "Default")
      (node (ref "U1") (pin "17") (pinfunction "TXD_17") (pintype "bidirectional"))
      (node (ref "U3") (pin "24") (pinfunction "PA1_24") (pintype "input"))
    )
    (net (code "49") (name "VREF+") (class "Default")
      (node (ref "C17") (pin "2") (pinfunction "2_2") (pintype "input"))
      (node (ref "U3") (pin "21") (pinfunction "VREF+_21") (pintype "input"))
    )
    (net (code "50") (name "VSYS") (class "Default")
      (node (ref "J4") (pin "5") (pinfunction "1_5") (pintype "input"))
      (node (ref "R24") (pin "2") (pinfunction "2_2") (pintype "input"))
    )
    (net (code "51") (name "VSYS_IN") (class "Default")
      (node (ref "R24") (pin "1") (pinfunction "1_1") (pintype "input"))
      (node (ref "R25") (pin "2") (pinfunction "2_2") (pintype "input"))
      (node (ref "U3") (pin "58") (pinfunction "PD11_58") (pintype "input"))
    )
    (net (code "52") (name "V_BCKP") (class "Default")
      (node (ref "BT1") (pin "+") (pinfunction "+_+") (pintype "bidirectional"))
      (node (ref "C6") (pin "2") (pinfunction "2_2") (pintype "input"))
      (node (ref "R7") (pin "1") (pinfunction "1_1") (pintype "input"))
      (node (ref "U2") (pin "22") (pinfunction "V_BCKP_22") (pintype "input"))
    )
    (net (code "53") (name "XLNA") (class "Default")
      (node (ref "C") (pin "1") (pinfunction "1_1") (pintype "input"))
      (node (ref "C28") (pin "2") (pinfunction "2_2") (pintype "input"))
    )
    (net (code "54") (name "unconnected-(U1-AF_OUT-Pad3)") (class "Default")
      (node (ref "U1") (pin "3") (pinfunction "AF_OUT_3") (pintype "bidirectional+no_connect"))
    )
    (net (code "55") (name "unconnected-(U1-SQ-Pad1)") (class "Default")
      (node (ref "U1") (pin "1") (pinfunction "SQ_1") (pintype "bidirectional+no_connect"))
    )
    (net (code "56") (name "unconnected-(U2-LNA_EN-Pad14)") (class "Default")
      (node (ref "U2") (pin "14") (pinfunction "LNA_EN_14") (pintype "input+no_connect"))
    )
    (net (code "57") (name "unconnected-(U2-Reserved-Pad15)") (class "Default")
      (node (ref "U2") (pin "15") (pinfunction "Reserved_15") (pintype "input+no_connect"))
    )
    (net (code "58") (name "unconnected-(U2-Reserved-Pad16)") (class "Default")
      (node (ref "U2") (pin "16") (pinfunction "Reserved_16") (pintype "input+no_connect"))
    )
    (net (code "59") (name "unconnected-(U2-Reserved-Pad17)") (class "Default")
      (node (ref "U2") (pin "17") (pinfunction "Reserved_17") (pintype "input+no_connect"))
    )
    (net (code "60") (name "unconnected-(U2-SAFEBOOT_N-Pad1)") (class "Default")
      (node (ref "U2") (pin "1") (pinfunction "SAFEBOOT_N_1") (pintype "input+no_connect"))
    )
    (net (code "61") (name "unconnected-(U2-SCL{slash}SPI-SLK-Pad19)") (class "Default")
      (node (ref "U2") (pin "19") (pinfunction "SCL/SPI-SLK_19") (pintype "input+no_connect"))
    )
    (net (code "62") (name "unconnected-(U2-SDA{slash}SPCS_N-Pad18)") (class "Default")
      (node (ref "U2") (pin "18") (pinfunction "SDA/SPCS_N_18") (pintype "input+no_connect"))
    )
    (net (code "63") (name "unconnected-(U2-USB_DM-Pad5)") (class "Default")
      (node (ref "U2") (pin "5") (pinfunction "USB_DM_5") (pintype "input+no_connect"))
    )
    (net (code "64") (name "unconnected-(U2-USB_DP-Pad6)") (class "Default")
      (node (ref "U2") (pin "6") (pinfunction "USB_DP_6") (pintype "input+no_connect"))
    )
    (net (code "65") (name "unconnected-(U3-PA7-Pad32)") (class "Default")
      (node (ref "U3") (pin "32") (pinfunction "PA7_32") (pintype "input+no_connect"))
    )
    (net (code "66") (name "unconnected-(U3-PA8-Pad67)") (class "Default")
      (node (ref "U3") (pin "67") (pinfunction "PA8_67") (pintype "input+no_connect"))
    )
    (net (code "67") (name "unconnected-(U3-PA9-Pad68)") (class "Default")
      (node (ref "U3") (pin "68") (pinfunction "PA9_68") (pintype "input+no_connect"))
    )
    (net (code "68") (name "unconnected-(U3-PA10-Pad69)") (class "Default")
      (node (ref "U3") (pin "69") (pinfunction "PA10_69") (pintype "input+no_connect"))
    )
    (net (code "69") (name "unconnected-(U3-PA11-Pad70)") (class "Default")
      (node (ref "U3") (pin "70") (pinfunction "PA11_70") (pintype "input+no_connect"))
    )
    (net (code "70") (name "unconnected-(U3-PA12-Pad71)") (class "Default")
      (node (ref "U3") (pin "71") (pinfunction "PA12_71") (pintype "input+no_connect"))
    )
    (net (code "71") (name "unconnected-(U3-PA15-Pad77)") (class "Default")
      (node (ref "U3") (pin "77") (pinfunction "PA15_77") (pintype "input+no_connect"))
    )
    (net (code "72") (name "unconnected-(U3-PB1-Pad36)") (class "Default")
      (node (ref "U3") (pin "36") (pinfunction "PB1_36") (pintype "input+no_connect"))
    )
    (net (code "73") (name "unconnected-(U3-PB4-Pad90)") (class "Default")
      (node (ref "U3") (pin "90") (pinfunction "PB4_90") (pintype "input+no_connect"))
    )
    (net (code "74") (name "unconnected-(U3-PB5-Pad91)") (class "Default")
      (node (ref "U3") (pin "91") (pinfunction "PB5_91") (pintype "input+no_connect"))
    )
    (net (code "75") (name "unconnected-(U3-PB6-Pad92)") (class "Default")
      (node (ref "U3") (pin "92") (pinfunction "PB6_92") (pintype "input+no_connect"))
    )
    (net (code "76") (name "unconnected-(U3-PB7-Pad93)") (class "Default")
      (node (ref "U3") (pin "93") (pinfunction "PB7_93") (pintype "input+no_connect"))
    )
    (net (code "77") (name "unconnected-(U3-PB8-Pad95)") (class "Default")
      (node (ref "U3") (pin "95") (pinfunction "PB8_95") (pintype "input+no_connect"))
    )
    (net (code "78") (name "unconnected-(U3-PB9-Pad96)") (class "Default")
      (node (ref "U3") (pin "96") (pinfunction "PB9_96") (pintype "input+no_connect"))
    )
    (net (code "79") (name "unconnected-(U3-PB10-Pad47)") (class "Default")
      (node (ref "U3") (pin "47") (pinfunction "PB10_47") (pintype "input+no_connect"))
    )
    (net (code "80") (name "unconnected-(U3-PB12-Pad51)") (class "Default")
      (node (ref "U3") (pin "51") (pinfunction "PB12_51") (pintype "input+no_connect"))
    )
    (net (code "81") (name "unconnected-(U3-PB13-Pad52)") (class "Default")
      (node (ref "U3") (pin "52") (pinfunction "PB13_52") (pintype "input+no_connect"))
    )
    (net (code "82") (name "unconnected-(U3-PB14-Pad53)") (class "Default")
      (node (ref "U3") (pin "53") (pinfunction "PB14_53") (pintype "input+no_connect"))
    )
    (net (code "83") (name "unconnected-(U3-PC0-Pad15)") (class "Default")
      (node (ref "U3") (pin "15") (pinfunction "PC0_15") (pintype "input+no_connect"))
    )
    (net (code "84") (name "unconnected-(U3-PC2-Pad17)") (class "Default")
      (node (ref "U3") (pin "17") (pinfunction "PC2_17") (pintype "input+no_connect"))
    )
    (net (code "85") (name "unconnected-(U3-PC3-Pad18)") (class "Default")
      (node (ref "U3") (pin "18") (pinfunction "PC3_18") (pintype "input+no_connect"))
    )
    (net (code "86") (name "unconnected-(U3-PC6-Pad63)") (class "Default")
      (node (ref "U3") (pin "63") (pinfunction "PC6_63") (pintype "input+no_connect"))
    )
    (net (code "87") (name "unconnected-(U3-PC7-Pad64)") (class "Default")
      (node (ref "U3") (pin "64") (pinfunction "PC7_64") (pintype "input+no_connect"))
    )
    (net (code "88") (name "unconnected-(U3-PC8-Pad65)") (class "Default")
      (node (ref "U3") (pin "65") (pinfunction "PC8_65") (pintype "input+no_connect"))
    )
    (net (code "89") (name "unconnected-(U3-PC9-Pad66)") (class "Default")
      (node (ref "U3") (pin "66") (pinfunction "PC9_66") (pintype "input+no_connect"))
    )
    (net (code "90") (name "unconnected-(U3-PC10-Pad78)") (class "Default")
      (node (ref "U3") (pin "78") (pinfunction "PC10_78") (pintype "input+no_connect"))
    )
    (net (code "91") (name "unconnected-(U3-PC11-Pad79)") (class "Default")
      (node (ref "U3") (pin "79") (pinfunction "PC11_79") (pintype "input+no_connect"))
    )
    (net (code "92") (name "unconnected-(U3-PC12-Pad80)") (class "Default")
      (node (ref "U3") (pin "80") (pinfunction "PC12_80") (pintype "input+no_connect"))
    )
    (net (code "93") (name "unconnected-(U3-PC13-Pad7)") (class "Default")
      (node (ref "U3") (pin "7") (pinfunction "PC13_7") (pintype "input+no_connect"))
    )
    (net (code "94") (name "unconnected-(U3-PD0-Pad81)") (class "Default")
      (node (ref "U3") (pin "81") (pinfunction "PD0_81") (pintype "input+no_connect"))
    )
    (net (code "95") (name "unconnected-(U3-PD1-Pad82)") (class "Default")
      (node (ref "U3") (pin "82") (pinfunction "PD1_82") (pintype "input+no_connect"))
    )
    (net (code "96") (name "unconnected-(U3-PD2-Pad83)") (class "Default")
      (node (ref "U3") (pin "83") (pinfunction "PD2_83") (pintype "input+no_connect"))
    )
    (net (code "97") (name "unconnected-(U3-PD3-Pad84)") (class "Default")
      (node (ref "U3") (pin "84") (pinfunction "PD3_84") (pintype "input+no_connect"))
    )
    (net (code "98") (name "unconnected-(U3-PD4-Pad85)") (class "Default")
      (node (ref "U3") (pin "85") (pinfunction "PD4_85") (pintype "input+no_connect"))
    )
    (net (code "99") (name "unconnected-(U3-PD6-Pad87)") (class "Default")
      (node (ref "U3") (pin "87") (pinfunction "PD6_87") (pintype "input+no_connect"))
    )
    (net (code "100") (name "unconnected-(U3-PD7-Pad88)") (class "Default")
      (node (ref "U3") (pin "88") (pinfunction "PD7_88") (pintype "input+no_connect"))
    )
    (net (code "101") (name "unconnected-(U3-PD8-Pad55)") (class "Default")
      (node (ref "U3") (pin "55") (pinfunction "PD8_55") (pintype "input+no_connect"))
    )
    (net (code "102") (name "unconnected-(U3-PD9-Pad56)") (class "Default")
      (node (ref "U3") (pin "56") (pinfunction "PD9_56") (pintype "input+no_connect"))
    )
    (net (code "103") (name "unconnected-(U3-PD10-Pad57)") (class "Default")
      (node (ref "U3") (pin "57") (pinfunction "PD10_57") (pintype "input+no_connect"))
    )
    (net (code "104") (name "unconnected-(U3-PD12-Pad59)") (class "Default")
      (node (ref "U3") (pin "59") (pinfunction "PD12_59") (pintype "input+no_connect"))
    )
    (net (code "105") (name "unconnected-(U3-PD13-Pad60)") (class "Default")
      (node (ref "U3") (pin "60") (pinfunction "PD13_60") (pintype "input+no_connect"))
    )
    (net (code "106") (name "unconnected-(U3-PD14-Pad61)") (class "Default")
      (node (ref "U3") (pin "61") (pinfunction "PD14_61") (pintype "input+no_connect"))
    )
    (net (code "107") (name "unconnected-(U3-PD15-Pad62)") (class "Default")
      (node (ref "U3") (pin "62") (pinfunction "PD15_62") (pintype "input+no_connect"))
    )
    (net (code "108") (name "unconnected-(U3-PE0-Pad97)") (class "Default")
      (node (ref "U3") (pin "97") (pinfunction "PE0_97") (pintype "input+no_connect"))
    )
    (net (code "109") (name "unconnected-(U3-PE1-Pad98)") (class "Default")
      (node (ref "U3") (pin "98") (pinfunction "PE1_98") (pintype "input+no_connect"))
    )
    (net (code "110") (name "unconnected-(U3-PE2-Pad1)") (class "Default")
      (node (ref "U3") (pin "1") (pinfunction "PE2_1") (pintype "input+no_connect"))
    )
    (net (code "111") (name "unconnected-(U3-PE3-Pad2)") (class "Default")
      (node (ref "U3") (pin "2") (pinfunction "PE3_2") (pintype "input+no_connect"))
    )
    (net (code "112") (name "unconnected-(U3-PE4-Pad3)") (class "Default")
      (node (ref "U3") (pin "3") (pinfunction "PE4_3") (pintype "input+no_connect"))
    )
    (net (code "113") (name "unconnected-(U3-PE5-Pad4)") (class "Default")
      (node (ref "U3") (pin "4") (pinfunction "PE5_4") (pintype "input+no_connect"))
    )
    (net (code "114") (name "unconnected-(U3-PE6-Pad5)") (class "Default")
      (node (ref "U3") (pin "5") (pinfunction "PE6_5") (pintype "input+no_connect"))
    )
    (net (code "115") (name "unconnected-(U3-PE7-Pad38)") (class "Default")
      (node (ref "U3") (pin "38") (pinfunction "PE7_38") (pintype "input+no_connect"))
    )
    (net (code "116") (name "unconnected-(U3-PE8-Pad39)") (class "Default")
      (node (ref "U3") (pin "39") (pinfunction "PE8_39") (pintype "input+no_connect"))
    )
    (net (code "117") (name "unconnected-(U3-PE9-Pad40)") (class "Default")
      (node (ref "U3") (pin "40") (pinfunction "PE9_40") (pintype "input+no_connect"))
    )
    (net (code "118") (name "unconnected-(U3-PE10-Pad41)") (class "Default")
      (node (ref "U3") (pin "41") (pinfunction "PE10_41") (pintype "input+no_connect"))
    )
    (net (code "119") (name "unconnected-(U3-PE11-Pad42)") (class "Default")
      (node (ref "U3") (pin "42") (pinfunction "PE11_42") (pintype "input+no_connect"))
    )
    (net (code "120") (name "unconnected-(U3-PE12-Pad43)") (class "Default")
      (node (ref "U3") (pin "43") (pinfunction "PE12_43") (pintype "input+no_connect"))
    )
    (net (code "121") (name "unconnected-(U3-PE13-Pad44)") (class "Default")
      (node (ref "U3") (pin "44") (pinfunction "PE13_44") (pintype "input+no_connect"))
    )
    (net (code "122") (name "unconnected-(U3-PE14-Pad45)") (class "Default")
      (node (ref "U3") (pin "45") (pinfunction "PE14_45") (pintype "input+no_connect"))
    )
    (net (code "123") (name "unconnected-(U3-PE15-Pad46)") (class "Default")
      (node (ref "U3") (pin "46") (pinfunction "PE15_46") (pintype "input+no_connect"))
    )
    (net (code "124") (name "unconnected-(U3-VBAT-Pad6)") (class "Default")
      (node (ref "U3") (pin "6") (pinfunction "VBAT_6") (pintype "input+no_connect"))
    )
    (net (code "125") (name "unconnected-(X2-GND-Pad2)") (class "Default")
      (node (ref "X2") (pin "2") (pinfunction "GND_2") (pintype "input+no_connect"))
    )
    (net (code "126") (name "unconnected-(X2-GND-Pad4)") (class "Default")
      (node (ref "X2") (pin "4") (pinfunction "GND_4") (pintype "input+no_connect"))
    )
  )
)
